# 05_MISC.net
KiCad netlist of a schematic drawn in Altium Designer
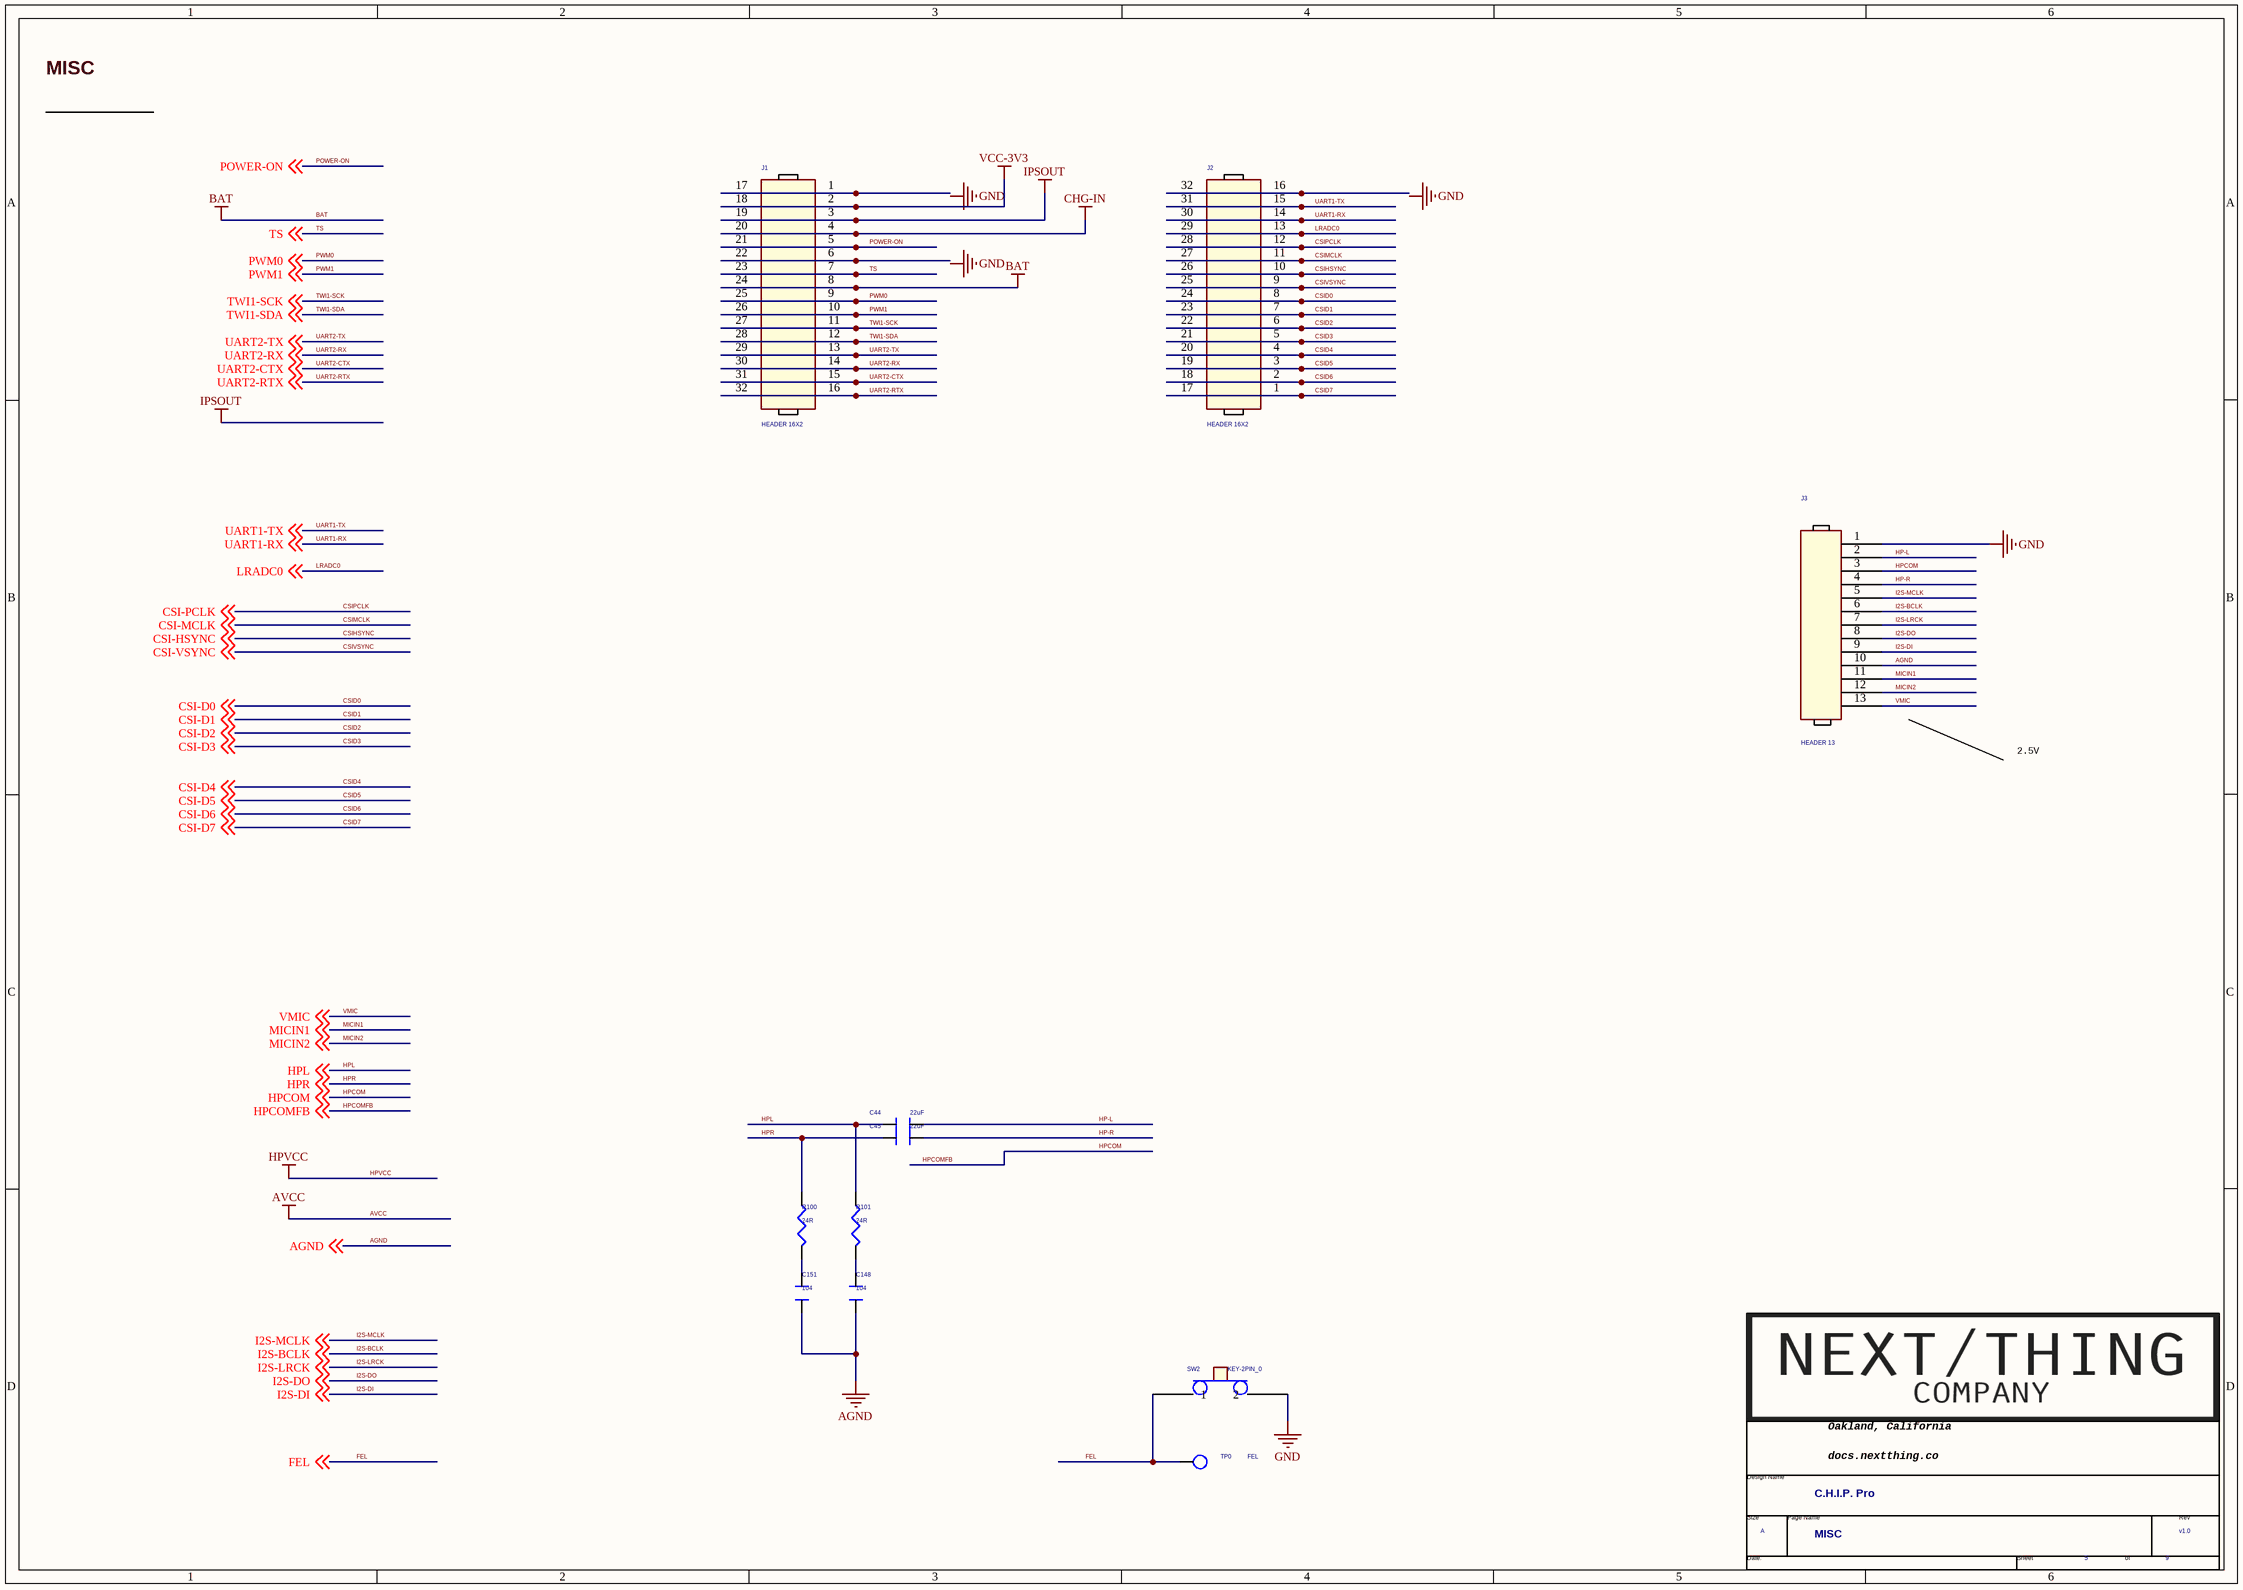
[diagram p0: 05 MISC.SchDoc]

(export (version "E")
  (design (tool "Eeschema 10.0.6"))
  (components
    (comp (ref "C44") (value "22uF") (footprint "C0805") (libsource (lib "*") (part "CAPACITOR_0")))
    (comp (ref "C45") (value "22uF") (footprint "C0805") (libsource (lib "*") (part "CAPACITOR_0")))
    (comp (ref "C148") (value "104") (footprint "C0201") (libsource (lib "*") (part "CAPACITOR_0_Dup1")))
    (comp (ref "C151") (value "104") (footprint "C0201") (libsource (lib "*") (part "CAPACITOR_0_Dup1")))
    (comp (ref "J1")
      (value "HEADER 16X2")
      (footprint "stampvia16")
      (libsource (lib "") (part "HEADER 16X2_0_1"))
    )
    (comp (ref "J2")
      (value "HEADER 16X2")
      (footprint "stampvia16")
      (libsource (lib "*") (part "HEADER 16X2_0"))
    )
    (comp (ref "J3") (value "HEADER 13") (footprint "stampvia13") (libsource (lib "*") (part "HEADER 13")))
    (comp (ref "R100") (value "24R") (footprint "R0402") (libsource (lib "*") (part "?_0")))
    (comp (ref "R101") (value "24R") (footprint "R0402") (libsource (lib "*") (part "?_0")))
    (comp (ref "SW2") (value "KEY-2PIN_0") (footprint "KEY-2") (libsource (lib "*") (part "KEY-2PIN_0")))
    (comp (ref "TP0") (value "FEL") (footprint "tp40_smd") (libsource (lib "*") (part "T_POINT_R")))
  )
  (nets
    (net (code "1") (name "/HP-L") (class "Default")
      (node (ref "C44") (pin "2") (pinfunction "2_2") (pintype "passive"))
      (node (ref "J3") (pin "2") (pinfunction "2_2") (pintype "passive"))
    )
    (net (code "2") (name "/HP-R") (class "Default")
      (node (ref "C45") (pin "2") (pinfunction "2_2") (pintype "passive"))
      (node (ref "J3") (pin "4") (pinfunction "4_4") (pintype "passive"))
    )
    (net (code "3") (name "AGND") (class "Default")
      (node (ref "C148") (pin "2") (pinfunction "2_2") (pintype "passive"))
      (node (ref "C151") (pin "2") (pinfunction "2_2") (pintype "passive"))
      (node (ref "J3") (pin "10") (pinfunction "10_10") (pintype "passive"))
    )
    (net (code "5") (name "BAT") (class "Default")
      (node (ref "J1") (pin "24") (pinfunction "24_24") (pintype "passive"))
      (node (ref "J1") (pin "8") (pinfunction "8_8") (pintype "passive"))
    )
    (net (code "6") (name "CHG-IN") (class "Default")
      (node (ref "J1") (pin "20") (pinfunction "20_20") (pintype "passive"))
      (node (ref "J1") (pin "4") (pinfunction "4_4") (pintype "passive"))
    )
    (net (code "7") (name "CSI-D0") (class "Default")
      (node (ref "J2") (pin "24") (pinfunction "24_24") (pintype "passive"))
      (node (ref "J2") (pin "8") (pinfunction "8_8") (pintype "passive"))
    )
    (net (code "8") (name "CSI-D1") (class "Default")
      (node (ref "J2") (pin "23") (pinfunction "23_23") (pintype "passive"))
      (node (ref "J2") (pin "7") (pinfunction "7_7") (pintype "passive"))
    )
    (net (code "9") (name "CSI-D2") (class "Default")
      (node (ref "J2") (pin "22") (pinfunction "22_22") (pintype "passive"))
      (node (ref "J2") (pin "6") (pinfunction "6_6") (pintype "passive"))
    )
    (net (code "10") (name "CSI-D3") (class "Default")
      (node (ref "J2") (pin "21") (pinfunction "21_21") (pintype "passive"))
      (node (ref "J2") (pin "5") (pinfunction "5_5") (pintype "passive"))
    )
    (net (code "11") (name "CSI-D4") (class "Default")
      (node (ref "J2") (pin "20") (pinfunction "20_20") (pintype "passive"))
      (node (ref "J2") (pin "4") (pinfunction "4_4") (pintype "passive"))
    )
    (net (code "12") (name "CSI-D5") (class "Default")
      (node (ref "J2") (pin "19") (pinfunction "19_19") (pintype "passive"))
      (node (ref "J2") (pin "3") (pinfunction "3_3") (pintype "passive"))
    )
    (net (code "13") (name "CSI-D6") (class "Default")
      (node (ref "J2") (pin "18") (pinfunction "18_18") (pintype "passive"))
      (node (ref "J2") (pin "2") (pinfunction "2_2") (pintype "passive"))
    )
    (net (code "14") (name "CSI-D7") (class "Default")
      (node (ref "J2") (pin "1") (pinfunction "1_1") (pintype "passive"))
      (node (ref "J2") (pin "17") (pinfunction "17_17") (pintype "passive"))
    )
    (net (code "15") (name "CSI-HSYNC") (class "Default")
      (node (ref "J2") (pin "10") (pinfunction "10_10") (pintype "passive"))
      (node (ref "J2") (pin "26") (pinfunction "26_26") (pintype "passive"))
    )
    (net (code "16") (name "CSI-MCLK") (class "Default")
      (node (ref "J2") (pin "11") (pinfunction "11_11") (pintype "passive"))
      (node (ref "J2") (pin "27") (pinfunction "27_27") (pintype "passive"))
    )
    (net (code "17") (name "CSI-PCLK") (class "Default")
      (node (ref "J2") (pin "12") (pinfunction "12_12") (pintype "passive"))
      (node (ref "J2") (pin "28") (pinfunction "28_28") (pintype "passive"))
    )
    (net (code "18") (name "CSI-VSYNC") (class "Default")
      (node (ref "J2") (pin "25") (pinfunction "25_25") (pintype "passive"))
      (node (ref "J2") (pin "9") (pinfunction "9_9") (pintype "passive"))
    )
    (net (code "19") (name "FEL") (class "Default")
      (node (ref "SW2") (pin "1") (pinfunction "1_1") (pintype "passive"))
      (node (ref "TP0") (pin "1") (pinfunction "TP_1") (pintype "passive"))
    )
    (net (code "20") (name "GND") (class "Default")
      (node (ref "J3") (pin "1") (pinfunction "1_1") (pintype "passive"))
      (node (ref "SW2") (pin "2") (pinfunction "2_2") (pintype "passive"))
    )
    (net (code "21") (name "HPCOM") (class "Default")
      (node (ref "J3") (pin "3") (pinfunction "3_3") (pintype "passive"))
    )
    (net (code "22") (name "HPL") (class "Default")
      (node (ref "C44") (pin "1") (pinfunction "1_1") (pintype "passive"))
      (node (ref "R101") (pin "1") (pinfunction "1_1") (pintype "passive"))
    )
    (net (code "23") (name "HPR") (class "Default")
      (node (ref "C45") (pin "1") (pinfunction "1_1") (pintype "passive"))
      (node (ref "R100") (pin "1") (pinfunction "1_1") (pintype "passive"))
    )
    (net (code "25") (name "I2S-BCLK") (class "Default")
      (node (ref "J3") (pin "6") (pinfunction "6_6") (pintype "passive"))
    )
    (net (code "26") (name "I2S-DI") (class "Default")
      (node (ref "J3") (pin "9") (pinfunction "9_9") (pintype "passive"))
    )
    (net (code "27") (name "I2S-DO") (class "Default")
      (node (ref "J3") (pin "8") (pinfunction "8_8") (pintype "passive"))
    )
    (net (code "28") (name "I2S-LRCK") (class "Default")
      (node (ref "J3") (pin "7") (pinfunction "7_7") (pintype "passive"))
    )
    (net (code "29") (name "I2S-MCLK") (class "Default")
      (node (ref "J3") (pin "5") (pinfunction "5_5") (pintype "passive"))
    )
    (net (code "30") (name "IPSOUT") (class "Default")
      (node (ref "J1") (pin "19") (pinfunction "19_19") (pintype "passive"))
      (node (ref "J1") (pin "3") (pinfunction "3_3") (pintype "passive"))
    )
    (net (code "31") (name "LRADC0") (class "Default")
      (node (ref "J2") (pin "13") (pinfunction "13_13") (pintype "passive"))
      (node (ref "J2") (pin "29") (pinfunction "29_29") (pintype "passive"))
    )
    (net (code "32") (name "MICIN1") (class "Default")
      (node (ref "J3") (pin "11") (pinfunction "11_11") (pintype "passive"))
    )
    (net (code "33") (name "MICIN2") (class "Default")
      (node (ref "J3") (pin "12") (pinfunction "12_12") (pintype "passive"))
    )
    (net (code "34") (name "Net-(C148-Pad1)") (class "Default")
      (node (ref "C148") (pin "1") (pinfunction "1_1") (pintype "passive"))
      (node (ref "R101") (pin "2") (pinfunction "2_2") (pintype "passive"))
    )
    (net (code "35") (name "Net-(C151-Pad1)") (class "Default")
      (node (ref "C151") (pin "1") (pinfunction "1_1") (pintype "passive"))
      (node (ref "R100") (pin "2") (pinfunction "2_2") (pintype "passive"))
    )
    (net (code "36") (name "Net-(J1-Pad1)") (class "Default")
      (node (ref "J1") (pin "1") (pinfunction "1_1") (pintype "passive"))
      (node (ref "J1") (pin "17") (pinfunction "17_17") (pintype "passive"))
    )
    (net (code "37") (name "Net-(J1-Pad22)") (class "Default")
      (node (ref "J1") (pin "22") (pinfunction "22_22") (pintype "passive"))
      (node (ref "J1") (pin "6") (pinfunction "6_6") (pintype "passive"))
    )
    (net (code "38") (name "Net-(J2-Pad16)") (class "Default")
      (node (ref "J2") (pin "16") (pinfunction "16_16") (pintype "passive"))
      (node (ref "J2") (pin "32") (pinfunction "32_32") (pintype "passive"))
    )
    (net (code "39") (name "POWER-ON") (class "Default")
      (node (ref "J1") (pin "21") (pinfunction "21_21") (pintype "passive"))
      (node (ref "J1") (pin "5") (pinfunction "5_5") (pintype "passive"))
    )
    (net (code "40") (name "PWM0") (class "Default")
      (node (ref "J1") (pin "25") (pinfunction "25_25") (pintype "passive"))
      (node (ref "J1") (pin "9") (pinfunction "9_9") (pintype "passive"))
    )
    (net (code "41") (name "PWM1") (class "Default")
      (node (ref "J1") (pin "10") (pinfunction "10_10") (pintype "passive"))
      (node (ref "J1") (pin "26") (pinfunction "26_26") (pintype "passive"))
    )
    (net (code "42") (name "TS") (class "Default")
      (node (ref "J1") (pin "23") (pinfunction "23_23") (pintype "passive"))
      (node (ref "J1") (pin "7") (pinfunction "7_7") (pintype "passive"))
    )
    (net (code "43") (name "TWI1-SCK") (class "Default")
      (node (ref "J1") (pin "11") (pinfunction "11_11") (pintype "passive"))
      (node (ref "J1") (pin "27") (pinfunction "27_27") (pintype "passive"))
    )
    (net (code "44") (name "TWI1-SDA") (class "Default")
      (node (ref "J1") (pin "12") (pinfunction "12_12") (pintype "passive"))
      (node (ref "J1") (pin "28") (pinfunction "28_28") (pintype "passive"))
    )
    (net (code "45") (name "UART1-RX") (class "Default")
      (node (ref "J2") (pin "14") (pinfunction "14_14") (pintype "passive"))
      (node (ref "J2") (pin "30") (pinfunction "30_30") (pintype "passive"))
    )
    (net (code "46") (name "UART1-TX") (class "Default")
      (node (ref "J2") (pin "15") (pinfunction "15_15") (pintype "passive"))
      (node (ref "J2") (pin "31") (pinfunction "31_31") (pintype "passive"))
    )
    (net (code "47") (name "UART2-CTX") (class "Default")
      (node (ref "J1") (pin "15") (pinfunction "15_15") (pintype "passive"))
      (node (ref "J1") (pin "31") (pinfunction "31_31") (pintype "passive"))
    )
    (net (code "48") (name "UART2-RTX") (class "Default")
      (node (ref "J1") (pin "16") (pinfunction "16_16") (pintype "passive"))
      (node (ref "J1") (pin "32") (pinfunction "32_32") (pintype "passive"))
    )
    (net (code "49") (name "UART2-RX") (class "Default")
      (node (ref "J1") (pin "14") (pinfunction "14_14") (pintype "passive"))
      (node (ref "J1") (pin "30") (pinfunction "30_30") (pintype "passive"))
    )
    (net (code "50") (name "UART2-TX") (class "Default")
      (node (ref "J1") (pin "13") (pinfunction "13_13") (pintype "passive"))
      (node (ref "J1") (pin "29") (pinfunction "29_29") (pintype "passive"))
    )
    (net (code "51") (name "VCC-3V3") (class "Default")
      (node (ref "J1") (pin "18") (pinfunction "18_18") (pintype "passive"))
      (node (ref "J1") (pin "2") (pinfunction "2_2") (pintype "passive"))
    )
    (net (code "52") (name "VMIC") (class "Default")
      (node (ref "J3") (pin "13") (pinfunction "13_13") (pintype "passive"))
    )
  )
)
